# TI_ADC_CURRENT.net
KiCad netlist of a schematic drawn in Altium Designer
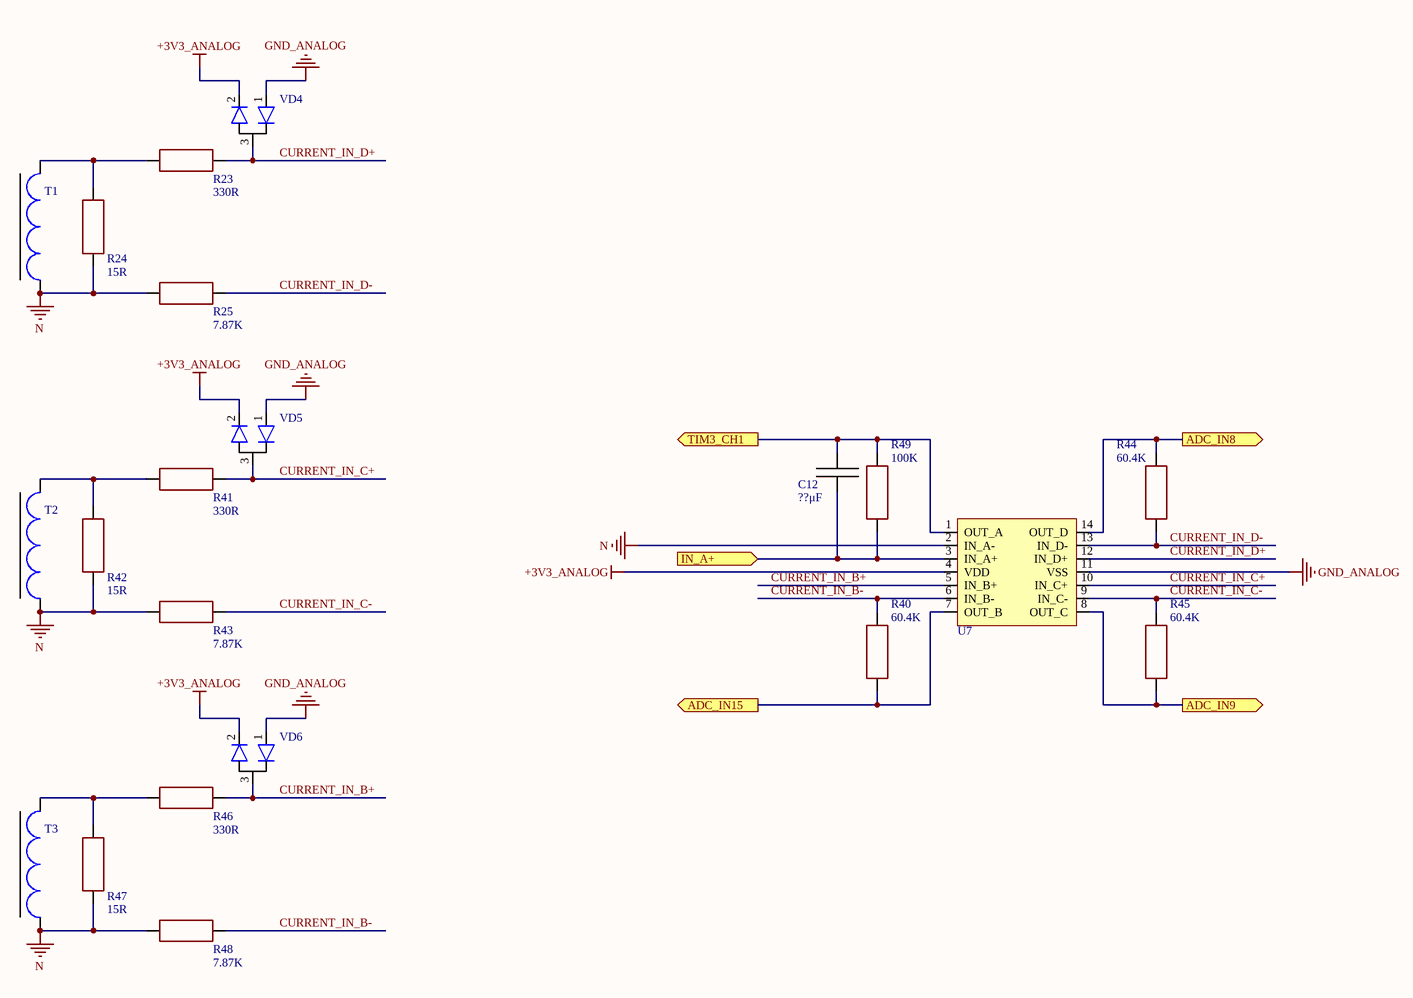
[diagram p0: TI_ADC_CURRENT.SchDoc]

(export (version "E")
  (design (tool "Eeschema 10.0.6"))
  (components
    (comp (ref "C12")
      (value "??μF")
      (footprint "CAP: 0603")
      (fields (field (name "VOLTAGE") "??V") (field (name "Comment") "Cap_0603"))
      (libsource (lib "capacitor") (part "Cap_0603"))
    )
    (comp (ref "R23")
      (value "330R")
      (footprint "RES: 0603")
      (fields
        (field (name "POWER") "0.1W")
        (field (name "TOLERANCE") "±5%")
        (field (name "Comment") "Resistor_0603")
      )
      (libsource (lib "") (part "Resistor_0603_1"))
    )
    (comp (ref "R24")
      (value "15R")
      (footprint "RES: 0603")
      (fields
        (field (name "POWER") "0.1W")
        (field (name "TOLERANCE") "±5%")
        (field (name "Comment") "Resistor_0603")
      )
      (libsource (lib "resistor") (part "Resistor_0603"))
    )
    (comp (ref "R25")
      (value "7.87K")
      (footprint "RES: 0603")
      (fields
        (field (name "POWER") "0.1W")
        (field (name "TOLERANCE") "±5%")
        (field (name "Comment") "Resistor_0603")
      )
      (libsource (lib "") (part "Resistor_0603_1"))
    )
    (comp (ref "R40")
      (value "60.4K")
      (footprint "RES: 0603")
      (fields
        (field (name "POWER") "0.1W")
        (field (name "TOLERANCE") "±5%")
        (field (name "Comment") "Resistor_0603")
      )
      (libsource (lib "resistor") (part "Resistor_0603"))
    )
    (comp (ref "R41")
      (value "330R")
      (footprint "RES: 0603")
      (fields
        (field (name "POWER") "0.1W")
        (field (name "TOLERANCE") "±5%")
        (field (name "Comment") "Resistor_0603")
      )
      (libsource (lib "") (part "Resistor_0603_1"))
    )
    (comp (ref "R42")
      (value "15R")
      (footprint "RES: 0603")
      (fields
        (field (name "POWER") "0.1W")
        (field (name "TOLERANCE") "±5%")
        (field (name "Comment") "Resistor_0603")
      )
      (libsource (lib "resistor") (part "Resistor_0603"))
    )
    (comp (ref "R43")
      (value "7.87K")
      (footprint "RES: 0603")
      (fields
        (field (name "POWER") "0.1W")
        (field (name "TOLERANCE") "±5%")
        (field (name "Comment") "Resistor_0603")
      )
      (libsource (lib "") (part "Resistor_0603_1"))
    )
    (comp (ref "R44")
      (value "60.4K")
      (footprint "RES: 0603")
      (fields
        (field (name "POWER") "0.1W")
        (field (name "TOLERANCE") "±5%")
        (field (name "Comment") "Resistor_0603")
      )
      (libsource (lib "resistor") (part "Resistor_0603"))
    )
    (comp (ref "R45")
      (value "60.4K")
      (footprint "RES: 0603")
      (fields
        (field (name "POWER") "0.1W")
        (field (name "TOLERANCE") "±5%")
        (field (name "Comment") "Resistor_0603")
      )
      (libsource (lib "resistor") (part "Resistor_0603"))
    )
    (comp (ref "R46")
      (value "330R")
      (footprint "RES: 0603")
      (fields
        (field (name "POWER") "0.1W")
        (field (name "TOLERANCE") "±5%")
        (field (name "Comment") "Resistor_0603")
      )
      (libsource (lib "") (part "Resistor_0603_1"))
    )
    (comp (ref "R47")
      (value "15R")
      (footprint "RES: 0603")
      (fields
        (field (name "POWER") "0.1W")
        (field (name "TOLERANCE") "±5%")
        (field (name "Comment") "Resistor_0603")
      )
      (libsource (lib "resistor") (part "Resistor_0603"))
    )
    (comp (ref "R48")
      (value "7.87K")
      (footprint "RES: 0603")
      (fields
        (field (name "POWER") "0.1W")
        (field (name "TOLERANCE") "±5%")
        (field (name "Comment") "Resistor_0603")
      )
      (libsource (lib "") (part "Resistor_0603_1"))
    )
    (comp (ref "R49")
      (value "100K")
      (footprint "RES: 0603")
      (fields
        (field (name "POWER") "0.1W")
        (field (name "TOLERANCE") "±5%")
        (field (name "Comment") "Resistor_0603")
      )
      (libsource (lib "") (part "Resistor_0603_1"))
    )
    (comp (ref "T1")
      (value "AC-1005")
      (footprint "AC-1005")
      (description "Current Transformer, primary current: 5A")
      (fields (field (name "MANUFACTURER") "Talema"))
      (libsource (lib "MY_INT_LIB") (part "AC-1005"))
    )
    (comp (ref "T2")
      (value "AC-1005")
      (footprint "AC-1005")
      (description "Current Transformer, primary current: 5A")
      (fields (field (name "MANUFACTURER") "Talema"))
      (libsource (lib "MY_INT_LIB") (part "AC-1005"))
    )
    (comp (ref "T3")
      (value "AC-1005")
      (footprint "AC-1005")
      (description "Current Transformer, primary current: 5A")
      (fields (field (name "MANUFACTURER") "Talema"))
      (libsource (lib "MY_INT_LIB") (part "AC-1005"))
    )
    (comp (ref "U7")
      (value "MCP6004")
      (footprint "SOIC-14")
      (description "1 MHz, Low-Power Op Amp")
      (fields (field (name "MANUFACTURER") "Microchip"))
      (libsource (lib "MY_INT_LIB") (part "MCP6004"))
    )
    (comp (ref "VD4")
      (value "BAV99")
      (footprint "SOT-23-3")
      (description "High-speed switching diode")
      (fields (field (name "MANUFACTURER") "Nexperia"))
      (libsource (lib "MY_INT_LIB") (part "BAV99"))
    )
    (comp (ref "VD5")
      (value "BAV99")
      (footprint "SOT-23-3")
      (description "High-speed switching diode")
      (fields (field (name "MANUFACTURER") "Nexperia"))
      (libsource (lib "MY_INT_LIB") (part "BAV99"))
    )
    (comp (ref "VD6")
      (value "BAV99")
      (footprint "SOT-23-3")
      (description "High-speed switching diode")
      (fields (field (name "MANUFACTURER") "Nexperia"))
      (libsource (lib "MY_INT_LIB") (part "BAV99"))
    )
  )
  (nets
    (net (code "1") (name "+3V3_ANALOG") (class "Default")
      (node (ref "U7") (pin "4") (pinfunction "VDD_4") (pintype "power_in"))
      (node (ref "VD4") (pin "2") (pintype "passive"))
      (node (ref "VD5") (pin "2") (pintype "passive"))
      (node (ref "VD6") (pin "2") (pintype "passive"))
    )
    (net (code "2") (name "/ADC_IN8") (class "Default")
      (node (ref "R44") (pin "2") (pinfunction "2_2") (pintype "passive"))
      (node (ref "U7") (pin "14") (pinfunction "OUT_D_14") (pintype "passive"))
    )
    (net (code "3") (name "/ADC_IN9") (class "Default")
      (node (ref "R45") (pin "1") (pinfunction "1_1") (pintype "passive"))
      (node (ref "U7") (pin "8") (pinfunction "OUT_C_8") (pintype "passive"))
    )
    (net (code "4") (name "/ADC_IN15") (class "Default")
      (node (ref "R40") (pin "1") (pinfunction "1_1") (pintype "passive"))
      (node (ref "U7") (pin "7") (pinfunction "OUT_B_7") (pintype "passive"))
    )
    (net (code "5") (name "/CURRENT_IN_B+") (class "Default")
      (node (ref "R46") (pin "2") (pinfunction "2_2") (pintype "passive"))
      (node (ref "U7") (pin "5") (pinfunction "IN_B+_5") (pintype "passive"))
      (node (ref "VD6") (pin "3") (pintype "passive"))
    )
    (net (code "6") (name "/CURRENT_IN_B-") (class "Default")
      (node (ref "R40") (pin "2") (pinfunction "2_2") (pintype "passive"))
      (node (ref "R48") (pin "2") (pinfunction "2_2") (pintype "passive"))
      (node (ref "U7") (pin "6") (pinfunction "IN_B-_6") (pintype "passive"))
    )
    (net (code "7") (name "/CURRENT_IN_C+") (class "Default")
      (node (ref "R41") (pin "2") (pinfunction "2_2") (pintype "passive"))
      (node (ref "U7") (pin "10") (pinfunction "IN_C+_10") (pintype "passive"))
      (node (ref "VD5") (pin "3") (pintype "passive"))
    )
    (net (code "8") (name "/CURRENT_IN_C-") (class "Default")
      (node (ref "R43") (pin "2") (pinfunction "2_2") (pintype "passive"))
      (node (ref "R45") (pin "2") (pinfunction "2_2") (pintype "passive"))
      (node (ref "U7") (pin "9") (pinfunction "IN_C-_9") (pintype "passive"))
    )
    (net (code "9") (name "/CURRENT_IN_D+") (class "Default")
      (node (ref "R23") (pin "2") (pinfunction "2_2") (pintype "passive"))
      (node (ref "U7") (pin "12") (pinfunction "IN_D+_12") (pintype "passive"))
      (node (ref "VD4") (pin "3") (pintype "passive"))
    )
    (net (code "10") (name "/CURRENT_IN_D-") (class "Default")
      (node (ref "R25") (pin "2") (pinfunction "2_2") (pintype "passive"))
      (node (ref "R44") (pin "1") (pinfunction "1_1") (pintype "passive"))
      (node (ref "U7") (pin "13") (pinfunction "IN_D-_13") (pintype "passive"))
    )
    (net (code "11") (name "/IN_A+") (class "Default")
      (node (ref "C12") (pin "2") (pinfunction "2_2") (pintype "passive"))
      (node (ref "R49") (pin "1") (pinfunction "1_1") (pintype "passive"))
      (node (ref "U7") (pin "3") (pinfunction "IN_A+_3") (pintype "passive"))
    )
    (net (code "12") (name "/TIM3_CH1") (class "Default")
      (node (ref "C12") (pin "1") (pinfunction "1_1") (pintype "passive"))
      (node (ref "R49") (pin "2") (pinfunction "2_2") (pintype "passive"))
      (node (ref "U7") (pin "1") (pinfunction "OUT_A_1") (pintype "passive"))
    )
    (net (code "13") (name "GND_ANALOG") (class "Default")
      (node (ref "U7") (pin "11") (pinfunction "VSS_11") (pintype "power_in"))
      (node (ref "VD4") (pin "1") (pintype "passive"))
      (node (ref "VD5") (pin "1") (pintype "passive"))
      (node (ref "VD6") (pin "1") (pintype "passive"))
    )
    (net (code "14") (name "N") (class "Default")
      (node (ref "R24") (pin "1") (pinfunction "1_1") (pintype "passive"))
      (node (ref "R25") (pin "1") (pinfunction "1_1") (pintype "passive"))
      (node (ref "R42") (pin "1") (pinfunction "1_1") (pintype "passive"))
      (node (ref "R43") (pin "1") (pinfunction "1_1") (pintype "passive"))
      (node (ref "R47") (pin "1") (pinfunction "1_1") (pintype "passive"))
      (node (ref "R48") (pin "1") (pinfunction "1_1") (pintype "passive"))
      (node (ref "T1") (pin "1") (pinfunction "1_1") (pintype "power_in"))
      (node (ref "T2") (pin "1") (pinfunction "1_1") (pintype "power_in"))
      (node (ref "T3") (pin "1") (pinfunction "1_1") (pintype "power_in"))
      (node (ref "U7") (pin "2") (pinfunction "IN_A-_2") (pintype "passive"))
    )
    (net (code "15") (name "Net-(R23-Pad1)") (class "Default")
      (node (ref "R23") (pin "1") (pinfunction "1_1") (pintype "passive"))
      (node (ref "R24") (pin "2") (pinfunction "2_2") (pintype "passive"))
      (node (ref "T1") (pin "2") (pinfunction "2_2") (pintype "power_in"))
    )
    (net (code "16") (name "Net-(R41-Pad1)") (class "Default")
      (node (ref "R41") (pin "1") (pinfunction "1_1") (pintype "passive"))
      (node (ref "R42") (pin "2") (pinfunction "2_2") (pintype "passive"))
      (node (ref "T2") (pin "2") (pinfunction "2_2") (pintype "power_in"))
    )
    (net (code "17") (name "Net-(R46-Pad1)") (class "Default")
      (node (ref "R46") (pin "1") (pinfunction "1_1") (pintype "passive"))
      (node (ref "R47") (pin "2") (pinfunction "2_2") (pintype "passive"))
      (node (ref "T3") (pin "2") (pinfunction "2_2") (pintype "power_in"))
    )
  )
)
